# ProPrj_stm32G474_PPO_Display_2026-05-16.net
KiCad netlist of a schematic drawn in EasyEDA Pro
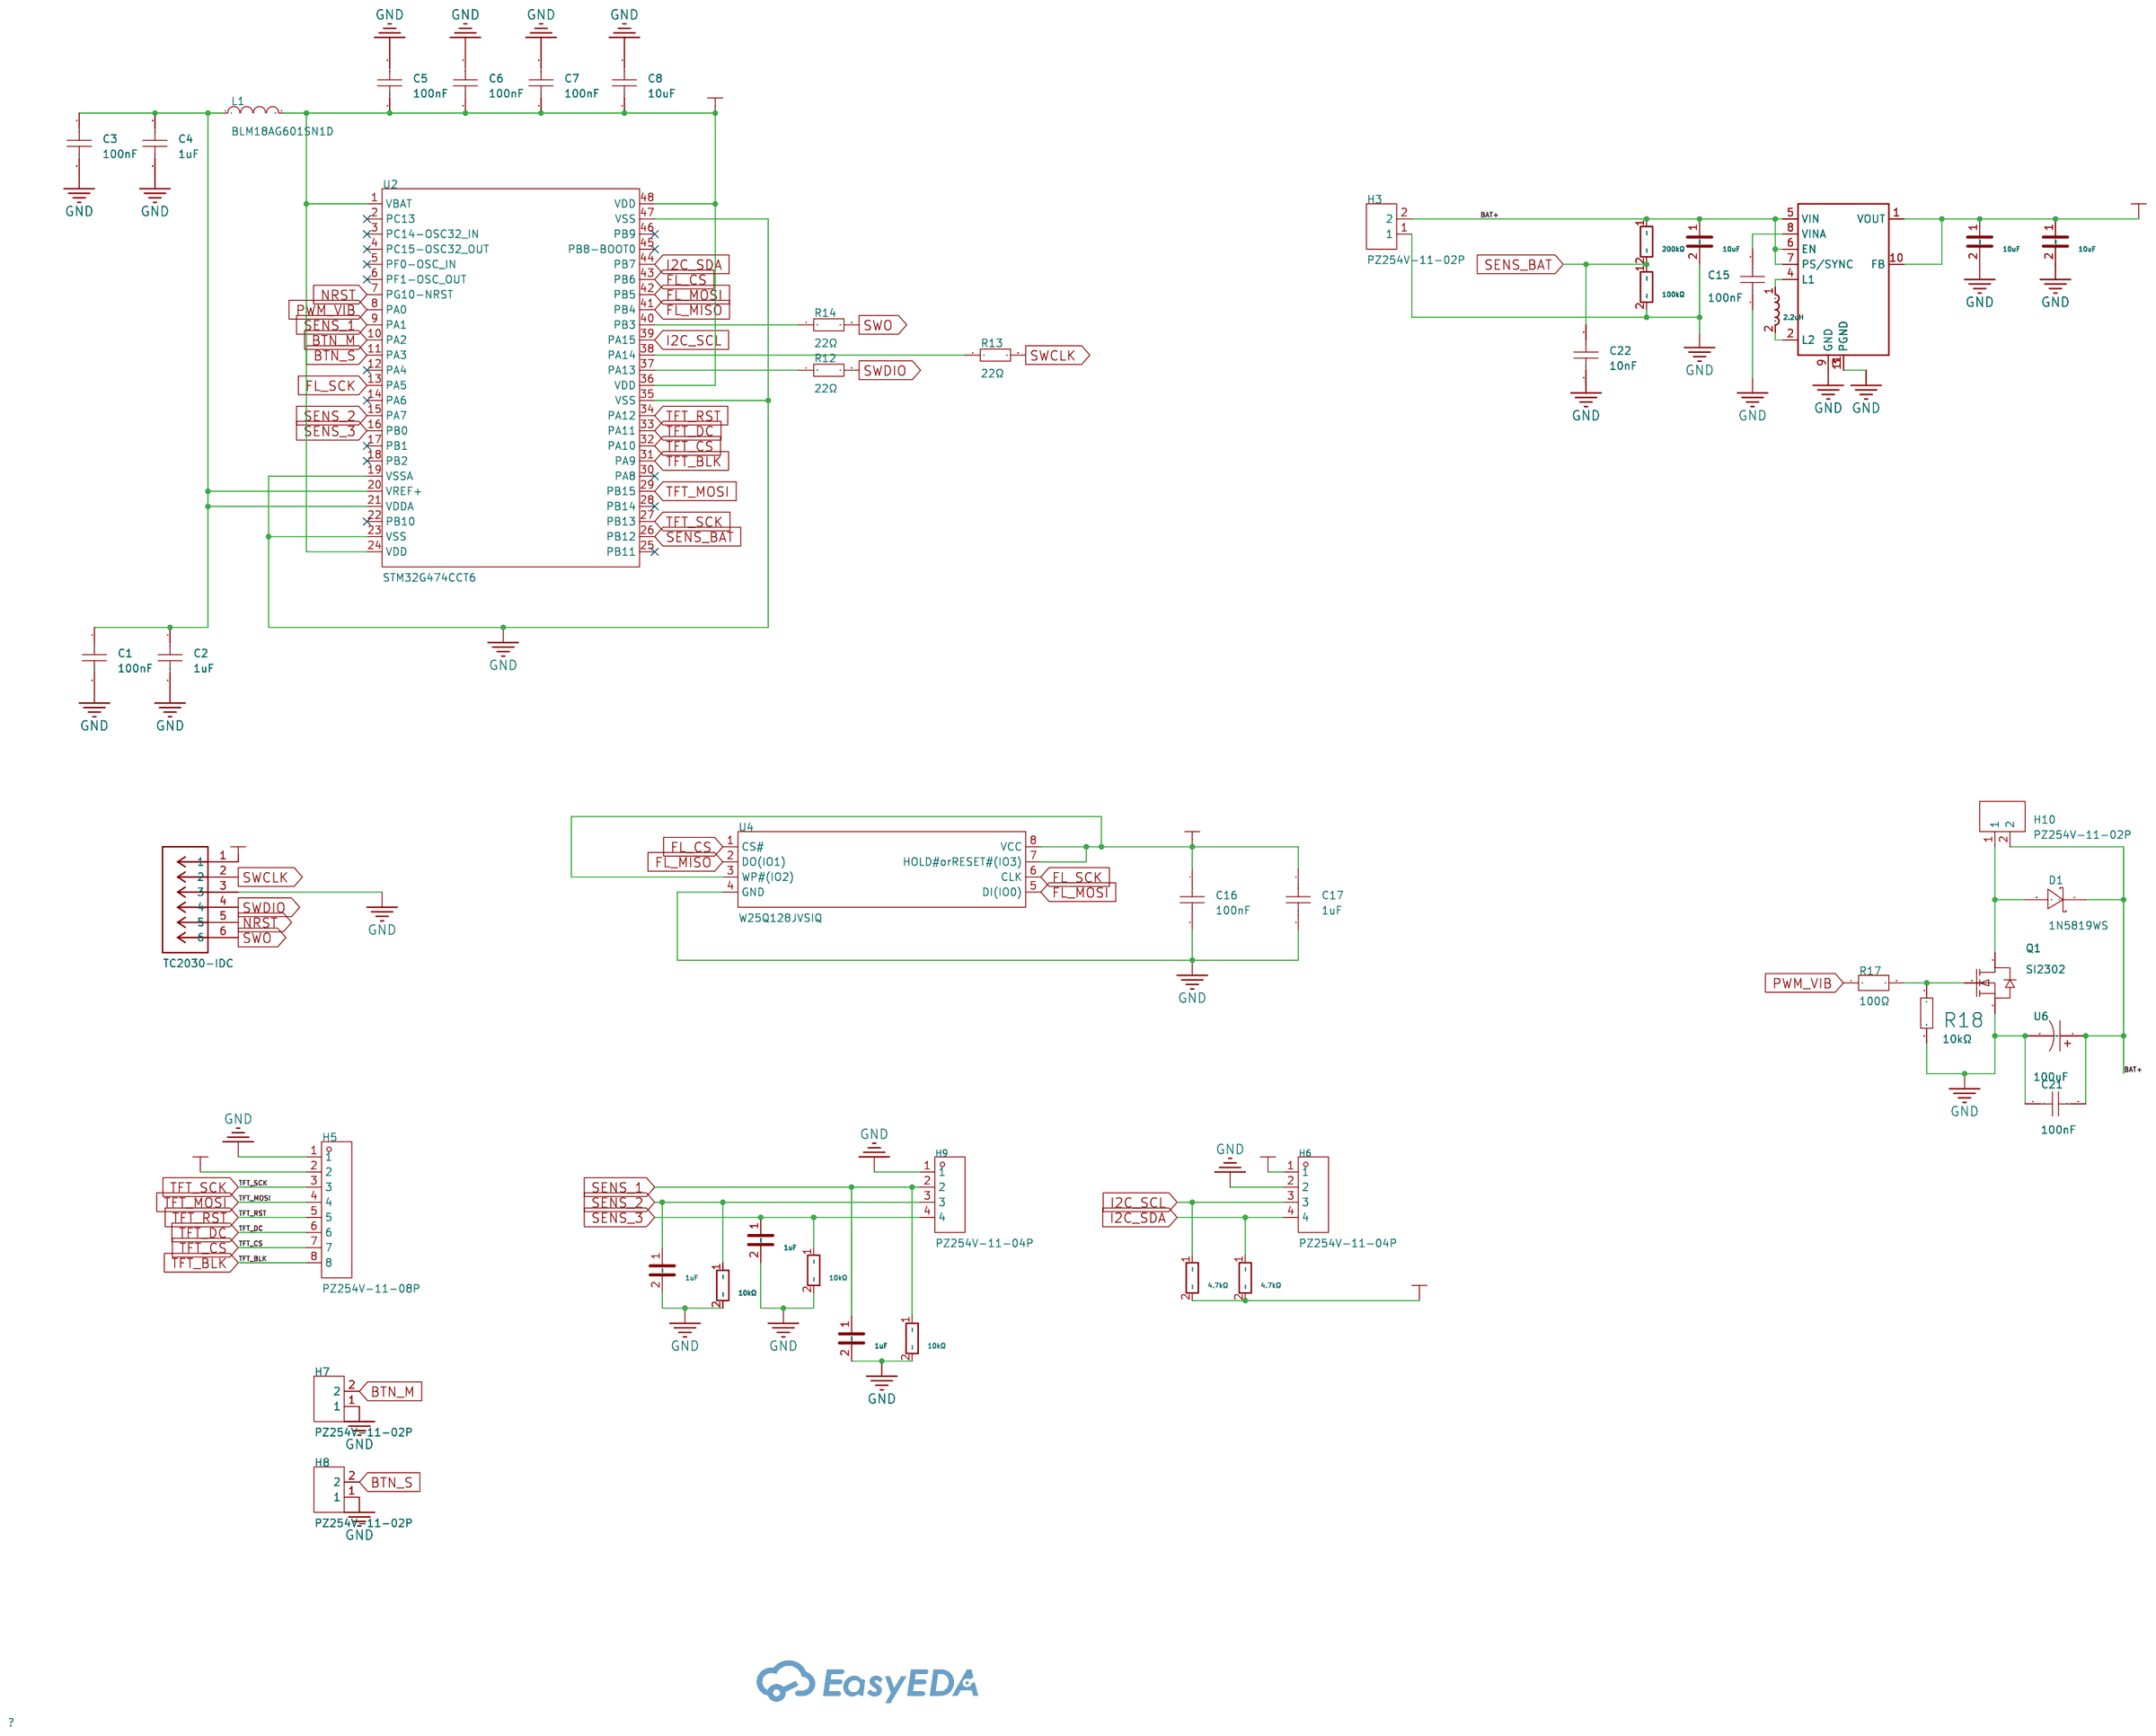
[diagram p0: schematic sheet]

(export (version "E")
  (design (tool "Eeschema 10.0.6"))
  (components
    (comp (ref "C1")
      (value "100nF")
      (footprint "easyedapro:C0603")
      (description "Capacitance:100nF Tolerance:±10% Tolerance:±10% Voltage Rating:50V Temperature Coefficient:X7R")
      (fields
        (field (name "Manufacturer Part") "CC0603KRX7R9BB104")
        (field (name "Manufacturer") "YAGEO(国巨)")
      )
      (libsource (lib "easyedapro") (part "CC0603KRX7R9BB104"))
    )
    (comp (ref "C2")
      (value "1uF")
      (footprint "easyedapro:C0603")
      (description "Capacitance:1uF Tolerance:±10% Tolerance:±10% Voltage Rating:50V Temperature Coefficient:X5R")
      (fields
        (field (name "Manufacturer Part") "CL10A105KB8NNNC")
        (field (name "Manufacturer") "SAMSUNG(三星)")
      )
      (libsource (lib "easyedapro") (part "CL10A105KB8NNNC"))
    )
    (comp (ref "C3")
      (value "100nF")
      (footprint "easyedapro:C0603")
      (description "Capacitance:100nF Tolerance:±10% Tolerance:±10% Voltage Rating:50V Temperature Coefficient:X7R")
      (fields
        (field (name "Manufacturer Part") "CC0603KRX7R9BB104")
        (field (name "Manufacturer") "YAGEO(国巨)")
      )
      (libsource (lib "easyedapro") (part "CC0603KRX7R9BB104"))
    )
    (comp (ref "C4")
      (value "1uF")
      (footprint "easyedapro:C0603")
      (description "Capacitance:1uF Tolerance:±10% Tolerance:±10% Voltage Rating:50V Temperature Coefficient:X5R")
      (fields
        (field (name "Manufacturer Part") "CL10A105KB8NNNC")
        (field (name "Manufacturer") "SAMSUNG(三星)")
      )
      (libsource (lib "easyedapro") (part "CL10A105KB8NNNC"))
    )
    (comp (ref "C5")
      (value "100nF")
      (footprint "easyedapro:C0603")
      (description "Capacitance:100nF Tolerance:±10% Tolerance:±10% Voltage Rating:50V Temperature Coefficient:X7R")
      (fields
        (field (name "Manufacturer Part") "CC0603KRX7R9BB104")
        (field (name "Manufacturer") "YAGEO(国巨)")
      )
      (libsource (lib "easyedapro") (part "CC0603KRX7R9BB104"))
    )
    (comp (ref "C6")
      (value "100nF")
      (footprint "easyedapro:C0603")
      (description "Capacitance:100nF Tolerance:±10% Tolerance:±10% Voltage Rating:50V Temperature Coefficient:X7R")
      (fields
        (field (name "Manufacturer Part") "CC0603KRX7R9BB104")
        (field (name "Manufacturer") "YAGEO(国巨)")
      )
      (libsource (lib "easyedapro") (part "CC0603KRX7R9BB104"))
    )
    (comp (ref "C7")
      (value "100nF")
      (footprint "easyedapro:C0603")
      (description "Capacitance:100nF Tolerance:±10% Tolerance:±10% Voltage Rating:50V Temperature Coefficient:X7R")
      (fields
        (field (name "Manufacturer Part") "CC0603KRX7R9BB104")
        (field (name "Manufacturer") "YAGEO(国巨)")
      )
      (libsource (lib "easyedapro") (part "CC0603KRX7R9BB104"))
    )
    (comp (ref "C8")
      (value "10uF")
      (footprint "easyedapro:C0603")
      (description "Capacitance:10uF Tolerance:±20% Tolerance:±20% Voltage Rating:6.3V Temperature Coefficient:X5R")
      (fields
        (field (name "Manufacturer Part") "CL10A106MQ8NNNC")
        (field (name "Manufacturer") "SAMSUNG(三星)")
      )
      (libsource (lib "easyedapro") (part "CL10A106MQ8NNNC"))
    )
    (comp (ref "C9")
      (value "1uF")
      (footprint "easyedapro:Capacitor_SMD:C_0603_1608Metric")
      (description "Capacitance:1uF Tolerance:±10% Tolerance:±10% Voltage Rating:50V Temperature Coefficient:X7R")
      (fields
        (field (name "Manufacturer Part") "CL10B105KB8NQNC")
        (field (name "Manufacturer") "SAMSUNG(三星)")
      )
      (libsource (lib "easyedapro") (part "Device_C"))
    )
    (comp (ref "C10")
      (value "10uF")
      (footprint "easyedapro:Capacitor_SMD:C_0603_1608Metric")
      (description "Capacitance:10uF Tolerance:±20% Tolerance:±20% Voltage Rating:6.3V Temperature Coefficient:X5R")
      (fields
        (field (name "Manufacturer Part") "CL10A106MQ8NNNC")
        (field (name "Manufacturer") "SAMSUNG(三星)")
      )
      (libsource (lib "easyedapro") (part "Device_C"))
    )
    (comp (ref "C11")
      (value "10uF")
      (footprint "easyedapro:Capacitor_SMD:C_0603_1608Metric")
      (description "Capacitance:10uF Tolerance:±20% Tolerance:±20% Voltage Rating:25V Temperature Coefficient:X5R")
      (fields
        (field (name "Manufacturer Part") "CL10A106MA8NRNC")
        (field (name "Manufacturer") "SAMSUNG(三星)")
      )
      (libsource (lib "easyedapro") (part "Device_C"))
    )
    (comp (ref "C15")
      (value "100nF")
      (footprint "easyedapro:C0603")
      (description "Capacitance:100nF Tolerance:±10% Tolerance:±10% Voltage Rating:50V Temperature Coefficient:X7R")
      (fields
        (field (name "Manufacturer Part") "CC0603KRX7R9BB104")
        (field (name "Manufacturer") "YAGEO(国巨)")
      )
      (libsource (lib "easyedapro") (part "CC0603KRX7R9BB104"))
    )
    (comp (ref "C16")
      (value "100nF")
      (footprint "easyedapro:C0603")
      (description "Capacitance:100nF Tolerance:±10% Tolerance:±10% Voltage Rating:50V Temperature Coefficient:X7R")
      (fields
        (field (name "Manufacturer Part") "CC0603KRX7R9BB104")
        (field (name "Manufacturer") "YAGEO(国巨)")
      )
      (libsource (lib "easyedapro") (part "CC0603KRX7R9BB104"))
    )
    (comp (ref "C17")
      (value "1uF")
      (footprint "easyedapro:C0603")
      (description "Capacitance:1uF Tolerance:±10% Tolerance:±10% Voltage Rating:50V Temperature Coefficient:X5R")
      (fields
        (field (name "Manufacturer Part") "CL10A105KB8NNNC")
        (field (name "Manufacturer") "SAMSUNG(三星)")
      )
      (libsource (lib "easyedapro") (part "CL10A105KB8NNNC"))
    )
    (comp (ref "C18")
      (value "10uF")
      (footprint "easyedapro:Capacitor_SMD:C_0603_1608Metric")
      (description "Capacitance:10uF Tolerance:±20% Tolerance:±20% Voltage Rating:25V Temperature Coefficient:X5R")
      (fields
        (field (name "Manufacturer Part") "CL10A106MA8NRNC")
        (field (name "Manufacturer") "SAMSUNG(三星)")
      )
      (libsource (lib "easyedapro") (part "Device_C"))
    )
    (comp (ref "C19")
      (value "1uF")
      (footprint "easyedapro:Capacitor_SMD:C_0603_1608Metric")
      (description "Capacitance:1uF Tolerance:±10% Tolerance:±10% Voltage Rating:50V Temperature Coefficient:X7R")
      (fields
        (field (name "Manufacturer Part") "CL10B105KB8NQNC")
        (field (name "Manufacturer") "SAMSUNG(三星)")
      )
      (libsource (lib "easyedapro") (part "Device_C"))
    )
    (comp (ref "C20")
      (value "1uF")
      (footprint "easyedapro:Capacitor_SMD:C_0603_1608Metric")
      (description "Capacitance:1uF Tolerance:±10% Tolerance:±10% Voltage Rating:50V Temperature Coefficient:X7R")
      (fields
        (field (name "Manufacturer Part") "CL10B105KB8NQNC")
        (field (name "Manufacturer") "SAMSUNG(三星)")
      )
      (libsource (lib "easyedapro") (part "Device_C"))
    )
    (comp (ref "C21")
      (value "100nF")
      (footprint "easyedapro:C0603")
      (description "Capacitance:100nF Tolerance:±10% Tolerance:±10% Voltage Rating:50V Temperature Coefficient:X7R")
      (fields
        (field (name "Manufacturer Part") "CC0603KRX7R9BB104")
        (field (name "Manufacturer") "YAGEO(国巨)")
      )
      (libsource (lib "easyedapro") (part "CC0603KRX7R9BB104"))
    )
    (comp (ref "C22")
      (value "10nF")
      (footprint "easyedapro:C0603")
      (description "Capacitance:10nF Tolerance:±10% Tolerance:±10% Voltage Rating:50V Temperature Coefficient:X7R")
      (fields
        (field (name "Manufacturer Part") "CL10B103KB8NNNC")
        (field (name "Manufacturer") "SAMSUNG(三星)")
      )
      (libsource (lib "easyedapro") (part "CC0603KRX7R9BB104"))
    )
    (comp (ref "D1")
      (value "1N5819WS")
      (footprint "easyedapro:SOD-323_L1.8-W1.3-LS2.5-RD")
      (fields (field (name "Manufacturer") "Hottech(合科泰)"))
      (libsource (lib "easyedapro") (part "1N5819WS"))
    )
    (comp (ref "H3")
      (value "PZ254V-11-02P")
      (footprint "easyedapro:HDR-TH_2P-P2.54-V-M")
      (fields (field (name "Manufacturer") "XFCN(兴飞)"))
      (libsource (lib "easyedapro") (part "PZ254V-11-02P"))
    )
    (comp (ref "H5")
      (value "PZ254V-11-08P")
      (footprint "easyedapro:HDR-TH_8P-P2.54-V-M")
      (fields (field (name "Manufacturer") "XFCN(兴飞)"))
      (libsource (lib "easyedapro") (part "PZ254V-11-08P"))
    )
    (comp (ref "H6")
      (value "PZ254V-11-04P")
      (footprint "easyedapro:HDR-TH_4P-P2.54-V-M")
      (fields (field (name "Manufacturer") "XFCN(兴飞)"))
      (libsource (lib "easyedapro") (part "PZ254V-11-04P_C2691448"))
    )
    (comp (ref "H7")
      (value "PZ254V-11-02P")
      (footprint "easyedapro:HDR-TH_2P-P2.54-V-M")
      (fields (field (name "Manufacturer") "XFCN(兴飞)"))
      (libsource (lib "easyedapro") (part "PZ254V-11-02P"))
    )
    (comp (ref "H8")
      (value "PZ254V-11-02P")
      (footprint "easyedapro:HDR-TH_2P-P2.54-V-M")
      (fields (field (name "Manufacturer") "XFCN(兴飞)"))
      (libsource (lib "easyedapro") (part "PZ254V-11-02P"))
    )
    (comp (ref "H9")
      (value "PZ254V-11-04P")
      (footprint "easyedapro:HDR-TH_4P-P2.54-V-M")
      (fields (field (name "Manufacturer") "XFCN(兴飞)"))
      (libsource (lib "easyedapro") (part "PZ254V-11-04P_C2691448"))
    )
    (comp (ref "H10")
      (value "PZ254V-11-02P")
      (footprint "easyedapro:HDR-TH_2P-P2.54-V-M")
      (fields (field (name "Manufacturer") "XFCN(兴飞)"))
      (libsource (lib "easyedapro") (part "PZ254V-11-02P"))
    )
    (comp (ref "L1")
      (value "BLM18AG601SN1D")
      (footprint "easyedapro:L0603")
      (fields (field (name "Manufacturer") "muRata(村田)"))
      (libsource (lib "easyedapro") (part "BLM18AG601SN1D"))
    )
    (comp (ref "L2")
      (value "2.2uH")
      (footprint "easyedapro:Inductor_SMD:L_0402_1005Metric")
      (fields (field (name "Manufacturer Part") "LQH3NPN2R2MMEL") (field (name "Manufacturer") "muRata(村田)"))
      (libsource (lib "easyedapro") (part "Device_L"))
    )
    (comp (ref "Q1")
      (value "SI2302")
      (footprint "easyedapro:SOT-23-3_L2.9-W1.3-P1.90-LS2.4-BR")
      (fields (field (name "Manufacturer") "FOSAN(富捷/富信)"))
      (libsource (lib "easyedapro") (part "SI2302_C20628873"))
    )
    (comp (ref "R7")
      (value "200kΩ")
      (footprint "easyedapro:Resistor_SMD:R_0201_0603Metric")
      (fields
        (field (name "Manufacturer Part") "0603WAF2003T5E")
        (field (name "Manufacturer") "UNI-ROYAL(厚声)")
      )
      (libsource (lib "easyedapro") (part "Device_R"))
    )
    (comp (ref "R8")
      (value "100kΩ")
      (footprint "easyedapro:Resistor_SMD:R_0201_0603Metric")
      (fields (field (name "Manufacturer Part") "FRC0603J104 TS") (field (name "Manufacturer") "FOJAN(富捷)"))
      (libsource (lib "easyedapro") (part "Device_R"))
    )
    (comp (ref "R11")
      (value "10kΩ")
      (footprint "easyedapro:Resistor_SMD:R_0201_0603Metric")
      (fields
        (field (name "Manufacturer Part") "0603WAF1002T5E")
        (field (name "Manufacturer") "UNI-ROYAL(厚声)")
      )
      (libsource (lib "easyedapro") (part "Device_R"))
    )
    (comp (ref "R12")
      (value "22Ω")
      (footprint "easyedapro:R0603")
      (fields
        (field (name "Manufacturer Part") "0603WAF220JT5E")
        (field (name "Manufacturer") "UNI-ROYAL(厚声)")
      )
      (libsource (lib "easyedapro") (part "0603WAF220JT5E"))
    )
    (comp (ref "R13")
      (value "22Ω")
      (footprint "easyedapro:R0603")
      (fields
        (field (name "Manufacturer Part") "0603WAF220JT5E")
        (field (name "Manufacturer") "UNI-ROYAL(厚声)")
      )
      (libsource (lib "easyedapro") (part "0603WAF220JT5E"))
    )
    (comp (ref "R14")
      (value "22Ω")
      (footprint "easyedapro:R0603")
      (fields
        (field (name "Manufacturer Part") "0603WAF220JT5E")
        (field (name "Manufacturer") "UNI-ROYAL(厚声)")
      )
      (libsource (lib "easyedapro") (part "0603WAF220JT5E"))
    )
    (comp (ref "R15")
      (value "10kΩ")
      (footprint "easyedapro:Resistor_SMD:R_0201_0603Metric")
      (fields
        (field (name "Manufacturer Part") "0603WAF1002T5E")
        (field (name "Manufacturer") "UNI-ROYAL(厚声)")
      )
      (libsource (lib "easyedapro") (part "Device_R"))
    )
    (comp (ref "R16")
      (value "10kΩ")
      (footprint "easyedapro:Resistor_SMD:R_0201_0603Metric")
      (fields
        (field (name "Manufacturer Part") "0603WAF1002T5E")
        (field (name "Manufacturer") "UNI-ROYAL(厚声)")
      )
      (libsource (lib "easyedapro") (part "Device_R"))
    )
    (comp (ref "R17")
      (value "100Ω")
      (footprint "easyedapro:R0603")
      (fields (field (name "Manufacturer Part") "FRC0603J101 TS") (field (name "Manufacturer") "FOJAN(富捷)"))
      (libsource (lib "easyedapro") (part "FRC0603J101 TS"))
    )
    (comp (ref "R18")
      (value "10kΩ")
      (footprint "easyedapro:R0603")
      (fields
        (field (name "Manufacturer Part") "0603WAF1002T5E")
        (field (name "Manufacturer") "UNI-ROYAL(厚声)")
      )
      (libsource (lib "easyedapro") (part "0603WAF1002T5E"))
    )
    (comp (ref "R19")
      (value "4.7kΩ")
      (footprint "easyedapro:Resistor_SMD:R_0201_0603Metric")
      (fields
        (field (name "Manufacturer Part") "0603WAF4701T5E")
        (field (name "Manufacturer") "UNI-ROYAL(厚声)")
      )
      (libsource (lib "easyedapro") (part "Device_R"))
    )
    (comp (ref "R20")
      (value "4.7kΩ")
      (footprint "easyedapro:Resistor_SMD:R_0201_0603Metric")
      (fields
        (field (name "Manufacturer Part") "0603WAF4701T5E")
        (field (name "Manufacturer") "UNI-ROYAL(厚声)")
      )
      (libsource (lib "easyedapro") (part "Device_R"))
    )
    (comp (ref "U2")
      (value "STM32G474CCT6")
      (footprint "easyedapro:LQFP-48_L7.0-W7.0-P0.50-LS9.0-BL")
      (fields (field (name "Manufacturer") "ST(意法半导体)"))
      (libsource (lib "easyedapro") (part "STM32G474CCT6"))
    )
    (comp (ref "U3")
      (value "TPS63031DSKR")
      (footprint "easyedapro:Package_SON:WSON-10-1EP_2.5x2.5mm_P0.5mm_EP1.2x2mm")
      (fields (field (name "Manufacturer") "TI(德州仪器)"))
      (libsource (lib "easyedapro") (part "Regulator_Switching_TPS63031DSK"))
    )
    (comp (ref "U4")
      (value "W25Q128JVSIQ")
      (footprint "easyedapro:SOIC-8_L5.3-W5.3-P1.27-LS8.0-BL")
      (fields (field (name "Manufacturer") "Winbond(华邦)"))
      (libsource (lib "easyedapro") (part "W25Q128JVSIQ"))
    )
    (comp (ref "U5") (value "TC2030-IDC") (libsource (lib "easyedapro") (part "TC2030-IDC")))
    (comp (ref "U6")
      (value "100uF")
      (footprint "easyedapro:CAP-SMD_BD5.0-L5.3-W5.3-LS6.3-FD")
      (description "Capacitance:100uF Tolerance:±20% Tolerance:±20% Voltage Rating:6.3V Temperature Coefficient:X5R")
      (fields
        (field (name "Manufacturer Part") "CL31A107MQHNNNE")
        (field (name "Manufacturer") "SAMSUNG(三星)")
      )
      (libsource (lib "easyedapro") (part "CK1A101M-CRD54_C3001231"))
    )
  )
  (nets
    (net (code "1") (name "/BAT+") (class "Default")
      (node (ref "C10") (pin "1") (pinfunction "~_1") (pintype "unspecified"))
      (node (ref "C21") (pin "2") (pinfunction "2_2") (pintype "unspecified"))
      (node (ref "D1") (pin "1") (pinfunction "K_1") (pintype "unspecified"))
      (node (ref "H10") (pin "2") (pinfunction "2_2") (pintype "unspecified"))
      (node (ref "H3") (pin "2") (pinfunction "2_2") (pintype "unspecified"))
      (node (ref "R7") (pin "1") (pinfunction "~_1") (pintype "unspecified"))
      (node (ref "U3") (pin "5") (pinfunction "VIN_5") (pintype "unspecified"))
      (node (ref "U3") (pin "6") (pinfunction "EN_6") (pintype "input"))
      (node (ref "U3") (pin "7") (pinfunction "PS/SYNC_7") (pintype "input"))
      (node (ref "U6") (pin "1") (pinfunction "1_1") (pintype "unspecified"))
    )
    (net (code "2") (name "BTN_M") (class "Default")
      (node (ref "H7") (pin "2") (pinfunction "2_2") (pintype "unspecified"))
      (node (ref "U2") (pin "10") (pinfunction "PA2_10") (pintype "unspecified"))
    )
    (net (code "3") (name "BTN_S") (class "Default")
      (node (ref "H8") (pin "2") (pinfunction "2_2") (pintype "unspecified"))
      (node (ref "U2") (pin "11") (pinfunction "PA3_11") (pintype "unspecified"))
    )
    (net (code "4") (name "FL_CS") (class "Default")
      (node (ref "U2") (pin "43") (pinfunction "PB6_43") (pintype "unspecified"))
      (node (ref "U4") (pin "1") (pinfunction "CS#_1") (pintype "unspecified"))
    )
    (net (code "5") (name "FL_MISO") (class "Default")
      (node (ref "U2") (pin "41") (pinfunction "PB4_41") (pintype "unspecified"))
      (node (ref "U4") (pin "2") (pinfunction "DO(IO1)_2") (pintype "unspecified"))
    )
    (net (code "6") (name "FL_MOSI") (class "Default")
      (node (ref "U2") (pin "42") (pinfunction "PB5_42") (pintype "unspecified"))
      (node (ref "U4") (pin "5") (pinfunction "DI(IO0)_5") (pintype "unspecified"))
    )
    (net (code "7") (name "FL_SCK") (class "Default")
      (node (ref "U2") (pin "13") (pinfunction "PA5_13") (pintype "unspecified"))
      (node (ref "U4") (pin "6") (pinfunction "CLK_6") (pintype "unspecified"))
    )
    (net (code "8") (name "GND") (class "Default")
      (node (ref "C1") (pin "2") (pinfunction "2_2") (pintype "unspecified"))
      (node (ref "C10") (pin "2") (pinfunction "~_2") (pintype "unspecified"))
      (node (ref "C11") (pin "2") (pinfunction "~_2") (pintype "unspecified"))
      (node (ref "C15") (pin "1") (pinfunction "1_1") (pintype "unspecified"))
      (node (ref "C16") (pin "2") (pinfunction "2_2") (pintype "unspecified"))
      (node (ref "C17") (pin "2") (pinfunction "2_2") (pintype "unspecified"))
      (node (ref "C18") (pin "2") (pinfunction "~_2") (pintype "unspecified"))
      (node (ref "C19") (pin "2") (pinfunction "~_2") (pintype "unspecified"))
      (node (ref "C2") (pin "2") (pinfunction "2_2") (pintype "unspecified"))
      (node (ref "C20") (pin "2") (pinfunction "~_2") (pintype "unspecified"))
      (node (ref "C21") (pin "1") (pinfunction "1_1") (pintype "unspecified"))
      (node (ref "C22") (pin "1") (pinfunction "1_1") (pintype "unspecified"))
      (node (ref "C3") (pin "2") (pinfunction "2_2") (pintype "unspecified"))
      (node (ref "C4") (pin "2") (pinfunction "2_2") (pintype "unspecified"))
      (node (ref "C5") (pin "1") (pinfunction "1_1") (pintype "unspecified"))
      (node (ref "C6") (pin "1") (pinfunction "1_1") (pintype "unspecified"))
      (node (ref "C7") (pin "1") (pinfunction "1_1") (pintype "unspecified"))
      (node (ref "C8") (pin "1") (pinfunction "1_1") (pintype "unspecified"))
      (node (ref "C9") (pin "2") (pinfunction "~_2") (pintype "unspecified"))
      (node (ref "H3") (pin "1") (pinfunction "1_1") (pintype "unspecified"))
      (node (ref "H5") (pin "1") (pinfunction "1_1") (pintype "unspecified"))
      (node (ref "H6") (pin "2") (pinfunction "2_2") (pintype "input"))
      (node (ref "H7") (pin "1") (pinfunction "1_1") (pintype "unspecified"))
      (node (ref "H8") (pin "1") (pinfunction "1_1") (pintype "unspecified"))
      (node (ref "H9") (pin "1") (pinfunction "1_1") (pintype "input"))
      (node (ref "Q1") (pin "2") (pinfunction "S_2") (pintype "unspecified"))
      (node (ref "R11") (pin "2") (pinfunction "~_2") (pintype "unspecified"))
      (node (ref "R15") (pin "2") (pinfunction "~_2") (pintype "unspecified"))
      (node (ref "R16") (pin "2") (pinfunction "~_2") (pintype "unspecified"))
      (node (ref "R18") (pin "2") (pinfunction "2_2") (pintype "input"))
      (node (ref "R8") (pin "2") (pinfunction "~_2") (pintype "unspecified"))
      (node (ref "U2") (pin "19") (pinfunction "VSSA_19") (pintype "unspecified"))
      (node (ref "U2") (pin "23") (pinfunction "VSS_23") (pintype "unspecified"))
      (node (ref "U2") (pin "35") (pinfunction "VSS_35") (pintype "unspecified"))
      (node (ref "U2") (pin "47") (pinfunction "VSS_47") (pintype "unspecified"))
      (node (ref "U3") (pin "11") (pinfunction "PGND_11") (pintype "unspecified"))
      (node (ref "U3") (pin "3") (pinfunction "PGND_3") (pintype "unspecified"))
      (node (ref "U3") (pin "9") (pinfunction "GND_9") (pintype "unspecified"))
      (node (ref "U4") (pin "4") (pinfunction "GND_4") (pintype "unspecified"))
      (node (ref "U5") (pin "3") (pinfunction "3_3") (pintype "unspecified"))
      (node (ref "U6") (pin "2") (pinfunction "2_2") (pintype "unspecified"))
    )
    (net (code "9") (name "I2C_SCL") (class "Default")
      (node (ref "H6") (pin "3") (pinfunction "3_3") (pintype "input"))
      (node (ref "R19") (pin "1") (pinfunction "~_1") (pintype "unspecified"))
      (node (ref "U2") (pin "39") (pinfunction "PA15_39") (pintype "unspecified"))
    )
    (net (code "10") (name "I2C_SDA") (class "Default")
      (node (ref "H6") (pin "4") (pinfunction "4_4") (pintype "input"))
      (node (ref "R20") (pin "1") (pinfunction "~_1") (pintype "unspecified"))
      (node (ref "U2") (pin "44") (pinfunction "PB7_44") (pintype "unspecified"))
    )
    (net (code "11") (name "NRST") (class "Default")
      (node (ref "U2") (pin "7") (pinfunction "PG10-NRST_7") (pintype "unspecified"))
      (node (ref "U5") (pin "5") (pinfunction "5_5") (pintype "unspecified"))
    )
    (net (code "12") (name "Net-(D1-A)") (class "Default")
      (node (ref "D1") (pin "2") (pinfunction "A_2") (pintype "unspecified"))
      (node (ref "H10") (pin "1") (pinfunction "1_1") (pintype "unspecified"))
      (node (ref "Q1") (pin "3") (pinfunction "D_3") (pintype "unspecified"))
    )
    (net (code "13") (name "Net-(Q1-G)") (class "Default")
      (node (ref "Q1") (pin "1") (pinfunction "G_1") (pintype "unspecified"))
      (node (ref "R17") (pin "2") (pinfunction "2_2") (pintype "unspecified"))
      (node (ref "R18") (pin "1") (pinfunction "1_1") (pintype "input"))
    )
    (net (code "14") (name "Net-(U2-PA13)") (class "Default")
      (node (ref "R12") (pin "1") (pinfunction "1_1") (pintype "input"))
      (node (ref "U2") (pin "37") (pinfunction "PA13_37") (pintype "unspecified"))
    )
    (net (code "15") (name "Net-(U2-PA14)") (class "Default")
      (node (ref "R13") (pin "1") (pinfunction "1_1") (pintype "input"))
      (node (ref "U2") (pin "38") (pinfunction "PA14_38") (pintype "unspecified"))
    )
    (net (code "16") (name "Net-(U2-PB3)") (class "Default")
      (node (ref "R14") (pin "1") (pinfunction "1_1") (pintype "input"))
      (node (ref "U2") (pin "40") (pinfunction "PB3_40") (pintype "unspecified"))
    )
    (net (code "17") (name "Net-(U2-VDDA)") (class "Default")
      (node (ref "C1") (pin "1") (pinfunction "1_1") (pintype "unspecified"))
      (node (ref "C2") (pin "1") (pinfunction "1_1") (pintype "unspecified"))
      (node (ref "C3") (pin "1") (pinfunction "1_1") (pintype "unspecified"))
      (node (ref "C4") (pin "1") (pinfunction "1_1") (pintype "unspecified"))
      (node (ref "L1") (pin "1") (pinfunction "1_1") (pintype "unspecified"))
      (node (ref "U2") (pin "20") (pinfunction "VREF+_20") (pintype "unspecified"))
      (node (ref "U2") (pin "21") (pinfunction "VDDA_21") (pintype "unspecified"))
    )
    (net (code "18") (name "Net-(U3-L1)") (class "Default")
      (node (ref "L2") (pin "1") (pinfunction "1_1") (pintype "unspecified"))
      (node (ref "U3") (pin "4") (pinfunction "L1_4") (pintype "input"))
    )
    (net (code "19") (name "Net-(U3-L2)") (class "Default")
      (node (ref "L2") (pin "2") (pinfunction "2_2") (pintype "unspecified"))
      (node (ref "U3") (pin "2") (pinfunction "L2_2") (pintype "input"))
    )
    (net (code "20") (name "Net-(U3-VINA)") (class "Default")
      (node (ref "C15") (pin "2") (pinfunction "2_2") (pintype "unspecified"))
      (node (ref "U3") (pin "8") (pinfunction "VINA_8") (pintype "unspecified"))
    )
    (net (code "21") (name "PWM_VIB") (class "Default")
      (node (ref "R17") (pin "1") (pinfunction "1_1") (pintype "unspecified"))
      (node (ref "U2") (pin "8") (pinfunction "PA0_8") (pintype "unspecified"))
    )
    (net (code "22") (name "SENS_1") (class "Default")
      (node (ref "C9") (pin "1") (pinfunction "~_1") (pintype "unspecified"))
      (node (ref "H9") (pin "2") (pinfunction "2_2") (pintype "input"))
      (node (ref "R16") (pin "1") (pinfunction "~_1") (pintype "unspecified"))
      (node (ref "U2") (pin "9") (pinfunction "PA1_9") (pintype "unspecified"))
    )
    (net (code "23") (name "SENS_2") (class "Default")
      (node (ref "C19") (pin "1") (pinfunction "~_1") (pintype "unspecified"))
      (node (ref "H9") (pin "3") (pinfunction "3_3") (pintype "input"))
      (node (ref "R11") (pin "1") (pinfunction "~_1") (pintype "unspecified"))
      (node (ref "U2") (pin "15") (pinfunction "PA7_15") (pintype "unspecified"))
    )
    (net (code "24") (name "SENS_3") (class "Default")
      (node (ref "C20") (pin "1") (pinfunction "~_1") (pintype "unspecified"))
      (node (ref "H9") (pin "4") (pinfunction "4_4") (pintype "input"))
      (node (ref "R15") (pin "1") (pinfunction "~_1") (pintype "unspecified"))
      (node (ref "U2") (pin "16") (pinfunction "PB0_16") (pintype "unspecified"))
    )
    (net (code "25") (name "SENS_BAT") (class "Default")
      (node (ref "C22") (pin "2") (pinfunction "2_2") (pintype "unspecified"))
      (node (ref "R7") (pin "2") (pinfunction "~_2") (pintype "unspecified"))
      (node (ref "R8") (pin "1") (pinfunction "~_1") (pintype "unspecified"))
      (node (ref "U2") (pin "26") (pinfunction "PB12_26") (pintype "unspecified"))
    )
    (net (code "26") (name "SWCLK") (class "Default")
      (node (ref "R13") (pin "2") (pinfunction "2_2") (pintype "input"))
      (node (ref "U5") (pin "2") (pinfunction "2_2") (pintype "unspecified"))
    )
    (net (code "27") (name "SWDIO") (class "Default")
      (node (ref "R12") (pin "2") (pinfunction "2_2") (pintype "input"))
      (node (ref "U5") (pin "4") (pinfunction "4_4") (pintype "unspecified"))
    )
    (net (code "28") (name "SWO") (class "Default")
      (node (ref "R14") (pin "2") (pinfunction "2_2") (pintype "input"))
      (node (ref "U5") (pin "6") (pinfunction "6_6") (pintype "unspecified"))
    )
    (net (code "29") (name "TFT_BLK") (class "Default")
      (node (ref "H5") (pin "8") (pinfunction "8_8") (pintype "unspecified"))
      (node (ref "U2") (pin "31") (pinfunction "PA9_31") (pintype "unspecified"))
    )
    (net (code "30") (name "TFT_CS") (class "Default")
      (node (ref "H5") (pin "7") (pinfunction "7_7") (pintype "unspecified"))
      (node (ref "U2") (pin "32") (pinfunction "PA10_32") (pintype "unspecified"))
    )
    (net (code "31") (name "TFT_DC") (class "Default")
      (node (ref "H5") (pin "6") (pinfunction "6_6") (pintype "unspecified"))
      (node (ref "U2") (pin "33") (pinfunction "PA11_33") (pintype "unspecified"))
    )
    (net (code "32") (name "TFT_MOSI") (class "Default")
      (node (ref "H5") (pin "4") (pinfunction "4_4") (pintype "unspecified"))
      (node (ref "U2") (pin "29") (pinfunction "PB15_29") (pintype "unspecified"))
    )
    (net (code "33") (name "TFT_RST") (class "Default")
      (node (ref "H5") (pin "5") (pinfunction "5_5") (pintype "unspecified"))
      (node (ref "U2") (pin "34") (pinfunction "PA12_34") (pintype "unspecified"))
    )
    (net (code "34") (name "TFT_SCK") (class "Default")
      (node (ref "H5") (pin "3") (pinfunction "3_3") (pintype "unspecified"))
      (node (ref "U2") (pin "27") (pinfunction "PB13_27") (pintype "unspecified"))
    )
    (net (code "35") (name "VDD") (class "Default")
      (node (ref "C11") (pin "1") (pinfunction "~_1") (pintype "unspecified"))
      (node (ref "C16") (pin "1") (pinfunction "1_1") (pintype "unspecified"))
      (node (ref "C17") (pin "1") (pinfunction "1_1") (pintype "unspecified"))
      (node (ref "C18") (pin "1") (pinfunction "~_1") (pintype "unspecified"))
      (node (ref "C5") (pin "2") (pinfunction "2_2") (pintype "unspecified"))
      (node (ref "C6") (pin "2") (pinfunction "2_2") (pintype "unspecified"))
      (node (ref "C7") (pin "2") (pinfunction "2_2") (pintype "unspecified"))
      (node (ref "C8") (pin "2") (pinfunction "2_2") (pintype "unspecified"))
      (node (ref "H5") (pin "2") (pinfunction "2_2") (pintype "unspecified"))
      (node (ref "H6") (pin "1") (pinfunction "1_1") (pintype "input"))
      (node (ref "L1") (pin "2") (pinfunction "2_2") (pintype "unspecified"))
      (node (ref "R19") (pin "2") (pinfunction "~_2") (pintype "unspecified"))
      (node (ref "R20") (pin "2") (pinfunction "~_2") (pintype "unspecified"))
      (node (ref "U2") (pin "1") (pinfunction "VBAT_1") (pintype "unspecified"))
      (node (ref "U2") (pin "24") (pinfunction "VDD_24") (pintype "unspecified"))
      (node (ref "U2") (pin "36") (pinfunction "VDD_36") (pintype "unspecified"))
      (node (ref "U2") (pin "48") (pinfunction "VDD_48") (pintype "unspecified"))
      (node (ref "U3") (pin "1") (pinfunction "VOUT_1") (pintype "unspecified"))
      (node (ref "U3") (pin "10") (pinfunction "FB_10") (pintype "input"))
      (node (ref "U4") (pin "3") (pinfunction "WP#(IO2)_3") (pintype "unspecified"))
      (node (ref "U4") (pin "7") (pinfunction "HOLD#orRESET#(IO3)_7") (pintype "unspecified"))
      (node (ref "U4") (pin "8") (pinfunction "VCC_8") (pintype "unspecified"))
      (node (ref "U5") (pin "1") (pinfunction "1_1") (pintype "unspecified"))
    )
    (net (code "36") (name "unconnected-(U2-PA4-Pad12)") (class "Default")
      (node (ref "U2") (pin "12") (pinfunction "PA4_12") (pintype "unspecified+no_connect"))
    )
    (net (code "37") (name "unconnected-(U2-PA6-Pad14)") (class "Default")
      (node (ref "U2") (pin "14") (pinfunction "PA6_14") (pintype "unspecified+no_connect"))
    )
    (net (code "38") (name "unconnected-(U2-PA8-Pad30)") (class "Default")
      (node (ref "U2") (pin "30") (pinfunction "PA8_30") (pintype "unspecified+no_connect"))
    )
    (net (code "39") (name "unconnected-(U2-PB1-Pad17)") (class "Default")
      (node (ref "U2") (pin "17") (pinfunction "PB1_17") (pintype "unspecified+no_connect"))
    )
    (net (code "40") (name "unconnected-(U2-PB2-Pad18)") (class "Default")
      (node (ref "U2") (pin "18") (pinfunction "PB2_18") (pintype "unspecified+no_connect"))
    )
    (net (code "41") (name "unconnected-(U2-PB8-BOOT0-Pad45)") (class "Default")
      (node (ref "U2") (pin "45") (pinfunction "PB8-BOOT0_45") (pintype "unspecified+no_connect"))
    )
    (net (code "42") (name "unconnected-(U2-PB9-Pad46)") (class "Default")
      (node (ref "U2") (pin "46") (pinfunction "PB9_46") (pintype "unspecified+no_connect"))
    )
    (net (code "43") (name "unconnected-(U2-PB10-Pad22)") (class "Default")
      (node (ref "U2") (pin "22") (pinfunction "PB10_22") (pintype "unspecified+no_connect"))
    )
    (net (code "44") (name "unconnected-(U2-PB11-Pad25)") (class "Default")
      (node (ref "U2") (pin "25") (pinfunction "PB11_25") (pintype "unspecified+no_connect"))
    )
    (net (code "45") (name "unconnected-(U2-PB14-Pad28)") (class "Default")
      (node (ref "U2") (pin "28") (pinfunction "PB14_28") (pintype "unspecified+no_connect"))
    )
    (net (code "46") (name "unconnected-(U2-PC13-Pad2)") (class "Default")
      (node (ref "U2") (pin "2") (pinfunction "PC13_2") (pintype "unspecified+no_connect"))
    )
    (net (code "47") (name "unconnected-(U2-PC14-OSC32_IN-Pad3)") (class "Default")
      (node (ref "U2") (pin "3") (pinfunction "PC14-OSC32_IN_3") (pintype "unspecified+no_connect"))
    )
    (net (code "48") (name "unconnected-(U2-PC15-OSC32_OUT-Pad4)") (class "Default")
      (node (ref "U2") (pin "4") (pinfunction "PC15-OSC32_OUT_4") (pintype "unspecified+no_connect"))
    )
    (net (code "49") (name "unconnected-(U2-PF0-OSC_IN-Pad5)") (class "Default")
      (node (ref "U2") (pin "5") (pinfunction "PF0-OSC_IN_5") (pintype "unspecified+no_connect"))
    )
    (net (code "50") (name "unconnected-(U2-PF1-OSC_OUT-Pad6)") (class "Default")
      (node (ref "U2") (pin "6") (pinfunction "PF1-OSC_OUT_6") (pintype "unspecified+no_connect"))
    )
  )
)
